# WIFI.net
KiCad netlist of a schematic drawn in Altium Designer
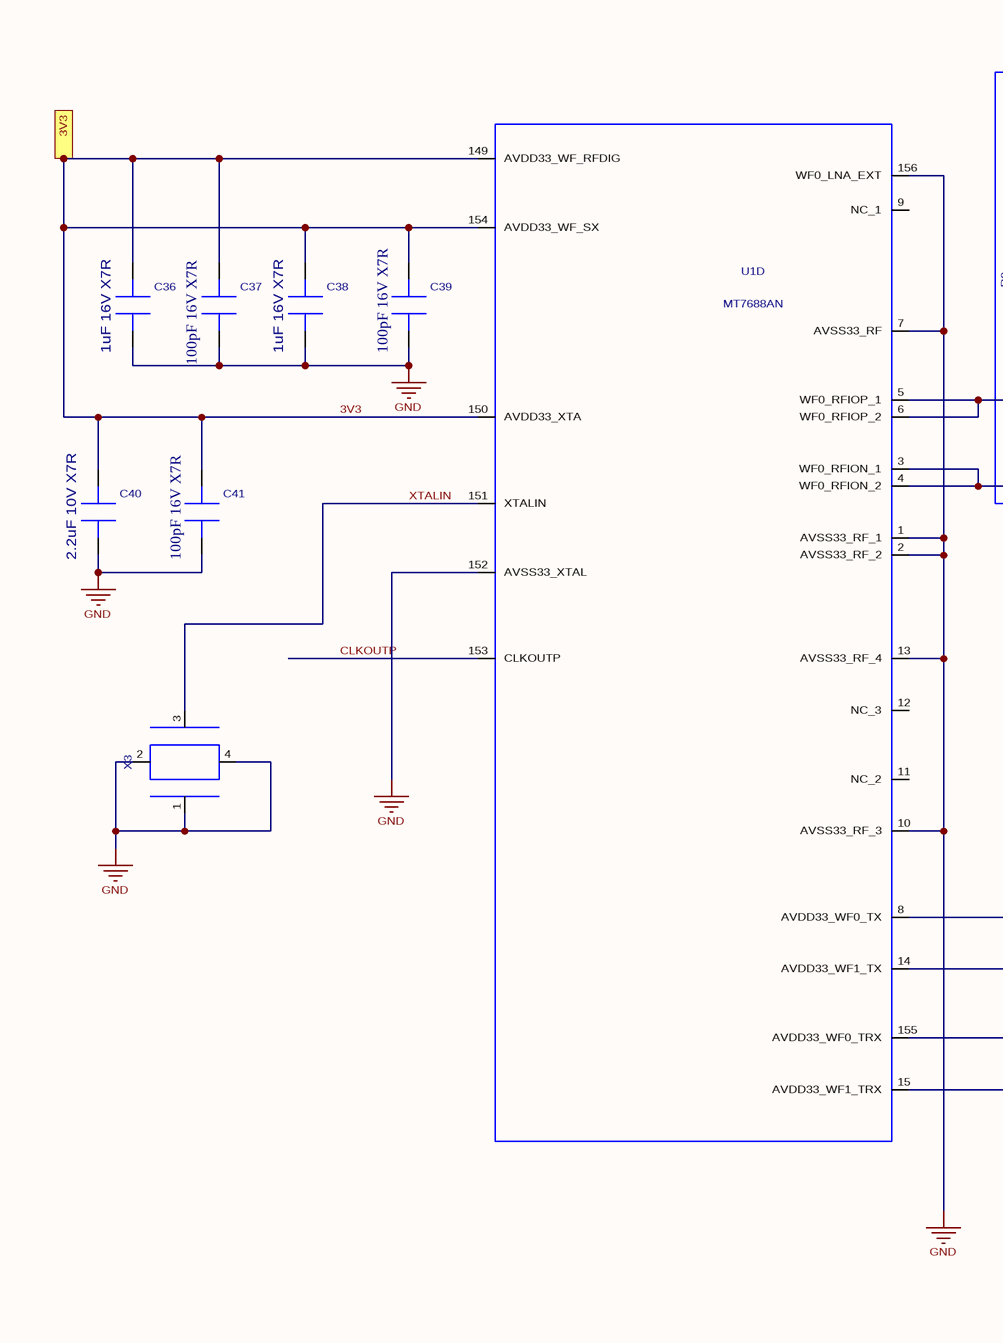
[diagram p0: WIFI.SchDoc, left]
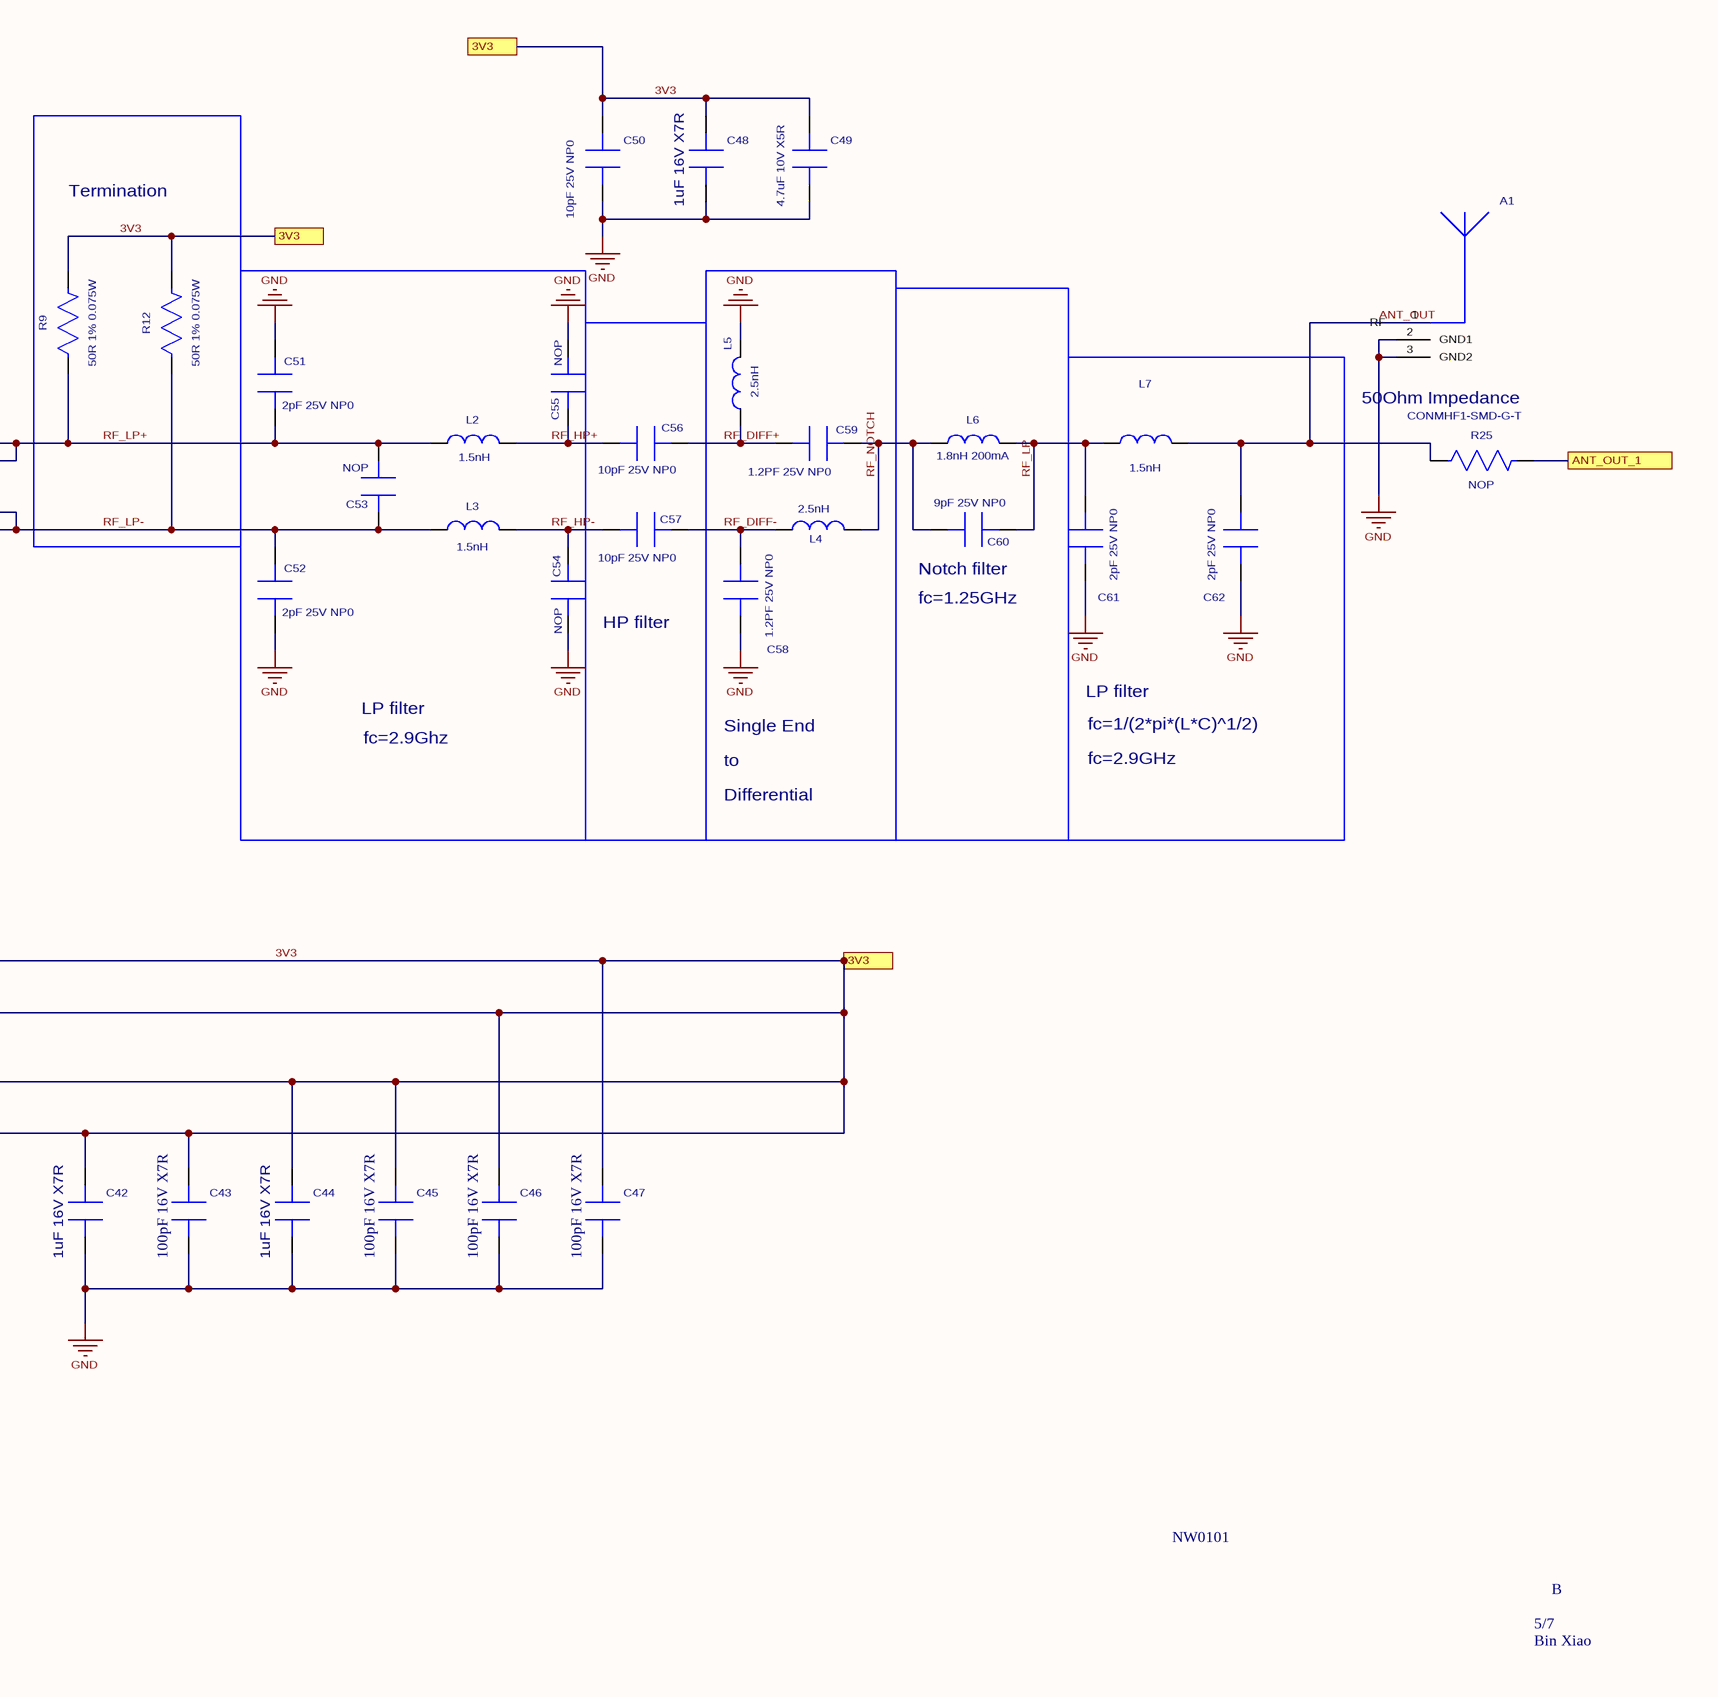
[diagram p1: WIFI.SchDoc, right]

(export (version "E")
  (design (tool "Eeschema 10.0.6"))
  (components
    (comp (ref "A1")
      (value "CONMHF1-SMD-G-T")
      (footprint "CONMHF1-SMD-G-T")
      (description "CONN UMC JACK STR SMD")
      (fields (field (name "MANUFACTURER") "Linx Technologies Inc."))
      (libsource (lib "*") (part "CONMHF1-SMD-G-T"))
    )
    (comp (ref "C36")
      (value "1uF 16V X7R")
      (footprint "C0402")
      (description "CAP CER 1UF 6.3V X7R 0402")
      (fields
        (field (name "PART NUMBER") "GRM155R70J105KA12D")
        (field (name "MANUFACTURER") "Murata Electronics")
      )
      (libsource (lib "NetworkModule") (part "CAP0402-105-6.3V-X7R"))
    )
    (comp (ref "C37")
      (value "100pF 16V X7R")
      (footprint "C0201")
      (description "CAP CER 100PF 16V X7R 0201")
      (fields
        (field (name "PART NUMBER") "0201B101K160CT")
        (field (name "MANUFACTURER") "Walsin Technology Corporation")
      )
      (libsource (lib "NetworkModule") (part "CAP0201-101-16V-X7R"))
    )
    (comp (ref "C38")
      (value "1uF 16V X7R")
      (footprint "C0402")
      (description "CAP CER 1UF 6.3V X7R 0402")
      (fields
        (field (name "PART NUMBER") "GRM155R70J105KA12D")
        (field (name "MANUFACTURER") "Murata Electronics")
      )
      (libsource (lib "NetworkModule") (part "CAP0402-105-6.3V-X7R"))
    )
    (comp (ref "C39")
      (value "100pF 16V X7R")
      (footprint "C0201")
      (description "CAP CER 100PF 16V X7R 0201")
      (fields
        (field (name "PART NUMBER") "0201B101K160CT")
        (field (name "MANUFACTURER") "Walsin Technology Corporation")
      )
      (libsource (lib "NetworkModule") (part "CAP0201-101-16V-X7R"))
    )
    (comp (ref "C40")
      (value "2.2uF 10V X7R")
      (footprint "C0402")
      (description "CAP CER 2.2UF 10V X7R 0402")
      (fields
        (field (name "PART NUMBER") "GRM155Z71A225KE01D")
        (field (name "MANUFACTURER") "Murata Electronics")
      )
      (libsource (lib "NetworkModule") (part "CAP0402-225-6.3V-X7R"))
    )
    (comp (ref "C41")
      (value "100pF 16V X7R")
      (footprint "C0201")
      (description "CAP CER 100PF 16V X7R 0201")
      (fields
        (field (name "PART NUMBER") "0201B101K160CT")
        (field (name "MANUFACTURER") "Walsin Technology Corporation")
      )
      (libsource (lib "NetworkModule") (part "CAP0201-101-16V-X7R"))
    )
    (comp (ref "C42")
      (value "1uF 16V X7R")
      (footprint "C0402")
      (description "CAP CER 1UF 6.3V X7R 0402")
      (fields
        (field (name "PART NUMBER") "GRM155R70J105KA12D")
        (field (name "MANUFACTURER") "Murata Electronics")
      )
      (libsource (lib "NetworkModule") (part "CAP0402-105-6.3V-X7R"))
    )
    (comp (ref "C43")
      (value "100pF 16V X7R")
      (footprint "C0201")
      (description "CAP CER 100PF 16V X7R 0201")
      (fields
        (field (name "PART NUMBER") "0201B101K160CT")
        (field (name "MANUFACTURER") "Walsin Technology Corporation")
      )
      (libsource (lib "NetworkModule") (part "CAP0201-101-16V-X7R"))
    )
    (comp (ref "C44")
      (value "1uF 16V X7R")
      (footprint "C0402")
      (description "CAP CER 1UF 6.3V X7R 0402")
      (fields
        (field (name "PART NUMBER") "GRM155R70J105KA12D")
        (field (name "MANUFACTURER") "Murata Electronics")
      )
      (libsource (lib "NetworkModule") (part "CAP0402-105-6.3V-X7R"))
    )
    (comp (ref "C45")
      (value "100pF 16V X7R")
      (footprint "C0201")
      (description "CAP CER 100PF 16V X7R 0201")
      (fields
        (field (name "PART NUMBER") "0201B101K160CT")
        (field (name "MANUFACTURER") "Walsin Technology Corporation")
      )
      (libsource (lib "NetworkModule") (part "CAP0201-101-16V-X7R"))
    )
    (comp (ref "C46")
      (value "100pF 16V X7R")
      (footprint "C0201")
      (description "CAP CER 100PF 16V X7R 0201")
      (fields
        (field (name "PART NUMBER") "0201B101K160CT")
        (field (name "MANUFACTURER") "Walsin Technology Corporation")
      )
      (libsource (lib "NetworkModule") (part "CAP0201-101-16V-X7R"))
    )
    (comp (ref "C47")
      (value "100pF 16V X7R")
      (footprint "C0201")
      (description "CAP CER 100PF 16V X7R 0201")
      (fields
        (field (name "PART NUMBER") "0201B101K160CT")
        (field (name "MANUFACTURER") "Walsin Technology Corporation")
      )
      (libsource (lib "NetworkModule") (part "CAP0201-101-16V-X7R"))
    )
    (comp (ref "C48")
      (value "1uF 16V X7R")
      (footprint "C0402")
      (description "CAP CER 1UF 6.3V X7R 0402")
      (fields
        (field (name "PART NUMBER") "GRM155R70J105KA12D")
        (field (name "MANUFACTURER") "Murata Electronics")
      )
      (libsource (lib "NetworkModule") (part "CAP0402-105-6.3V-X7R"))
    )
    (comp (ref "C49")
      (value "4.7uF 10V X5R")
      (footprint "C0402")
      (description "CAP CER 4.7UF 10V X5R 0402")
      (fields
        (field (name "PART NUMBER") "CL05A475MP5NRNC")
        (field (name "MANUFACTURER") "Samsung Electro-Mechanics")
      )
      (libsource (lib "NetworkModule") (part "CAP0402-475-10V-X5R"))
    )
    (comp (ref "C50")
      (value "10pF 25V NP0")
      (footprint "C0201")
      (description "CAP CER 10PF 25V C0G/NP0 0201")
      (fields
        (field (name "PART NUMBER") "0201N100J250CT")
        (field (name "MANUFACTURER") "Walsin Technology Corporation")
      )
      (libsource (lib "NetworkModule") (part "CAP0201-100-25V-NP0"))
    )
    (comp (ref "C51")
      (value "2pF 25V NP0")
      (footprint "C0201")
      (description "CAP CER 2PF 25V C0G/NP0 0201")
      (fields
        (field (name "PART NUMBER") "CL03C020BA3GNNC")
        (field (name "MANUFACTURER") "Samsung Electro-Mechanics")
      )
      (libsource (lib "NetworkModule") (part "CAP0201-020-25V-NP0"))
    )
    (comp (ref "C52")
      (value "2pF 25V NP0")
      (footprint "C0201")
      (description "CAP CER 2PF 25V C0G/NP0 0201")
      (fields
        (field (name "PART NUMBER") "CL03C020BA3GNNC")
        (field (name "MANUFACTURER") "Samsung Electro-Mechanics")
      )
      (libsource (lib "NetworkModule") (part "CAP0201-020-25V-NP0"))
    )
    (comp (ref "C53")
      (value "NOP")
      (footprint "C0201_NOP")
      (fields (field (name "Comment") "CAP0201-NOP"))
      (libsource (lib "NetworkModule") (part "CAP0201-NOP"))
    )
    (comp (ref "C54")
      (value "NOP")
      (footprint "C0201_NOP")
      (fields (field (name "Comment") "CAP0201-NOP"))
      (libsource (lib "NetworkModule") (part "CAP0201-NOP"))
    )
    (comp (ref "C55")
      (value "NOP")
      (footprint "C0201_NOP")
      (fields (field (name "Comment") "CAP0201-NOP"))
      (libsource (lib "NetworkModule") (part "CAP0201-NOP"))
    )
    (comp (ref "C56")
      (value "10pF 25V NP0")
      (footprint "C0201")
      (description "CAP CER 10PF 25V C0G/NP0 0201")
      (fields
        (field (name "PART NUMBER") "0201N100J250CT")
        (field (name "MANUFACTURER") "Walsin Technology Corporation")
      )
      (libsource (lib "NetworkModule") (part "CAP0201-100-25V-NP0"))
    )
    (comp (ref "C57")
      (value "10pF 25V NP0")
      (footprint "C0201")
      (description "CAP CER 10PF 25V C0G/NP0 0201")
      (fields
        (field (name "PART NUMBER") "0201N100J250CT")
        (field (name "MANUFACTURER") "Walsin Technology Corporation")
      )
      (libsource (lib "NetworkModule") (part "CAP0201-100-25V-NP0"))
    )
    (comp (ref "C58")
      (value "1.2PF 25V NP0")
      (footprint "C0201")
      (description "CAP CER 1.2PF 25V C0G/NP0 0201")
      (fields
        (field (name "PART NUMBER") "GRM0335C1E1R2WA01D")
        (field (name "MANUFACTURER") "Murata Electronics")
      )
      (libsource (lib "NetworkModule") (part "CAP0201-1R2-25V-NP0"))
    )
    (comp (ref "C59")
      (value "1.2PF 25V NP0")
      (footprint "C0201")
      (description "CAP CER 1.2PF 25V C0G/NP0 0201")
      (fields
        (field (name "PART NUMBER") "GRM0335C1E1R2WA01D")
        (field (name "MANUFACTURER") "Murata Electronics")
      )
      (libsource (lib "NetworkModule") (part "CAP0201-1R2-25V-NP0"))
    )
    (comp (ref "C60")
      (value "9pF 25V NP0")
      (footprint "C0201")
      (description "CAP CER 9PF 25V C0G 0201")
      (fields
        (field (name "PART NUMBER") "CGA1A2C0G1E090D030BA")
        (field (name "MANUFACTURER") "TDK Corporation")
      )
      (libsource (lib "NetworkModule") (part "CAP0201-090-100V-NP0"))
    )
    (comp (ref "C61")
      (value "2pF 25V NP0")
      (footprint "C0201")
      (description "CAP CER 2PF 25V C0G/NP0 0201")
      (fields
        (field (name "PART NUMBER") "CL03C020BA3GNNC")
        (field (name "MANUFACTURER") "Samsung Electro-Mechanics")
      )
      (libsource (lib "NetworkModule") (part "CAP0201-020-25V-NP0"))
    )
    (comp (ref "C62")
      (value "2pF 25V NP0")
      (footprint "C0201")
      (description "CAP CER 2PF 25V C0G/NP0 0201")
      (fields
        (field (name "PART NUMBER") "CL03C020BA3GNNC")
        (field (name "MANUFACTURER") "Samsung Electro-Mechanics")
      )
      (libsource (lib "NetworkModule") (part "CAP0201-020-25V-NP0"))
    )
    (comp (ref "L2")
      (value "1.5nH")
      (footprint "L0201")
      (description "INDUCTOR FIXED 1.5NH 0201")
      (fields
        (field (name "PART NUMBER") "WLCM0603TGB1N5TB")
        (field (name "MANUFACTURER") "Walsin Technology Corporation")
      )
      (libsource (lib "NetworkModule") (part "IND0201_1.5N_600MA"))
    )
    (comp (ref "L3")
      (value "1.5nH")
      (footprint "L0201")
      (description "INDUCTOR FIXED 1.5NH 0201")
      (fields
        (field (name "PART NUMBER") "WLCM0603TGB1N5TB")
        (field (name "MANUFACTURER") "Walsin Technology Corporation")
      )
      (libsource (lib "NetworkModule") (part "IND0201_1.5N_600MA"))
    )
    (comp (ref "L4")
      (value "2.5nH")
      (footprint "L0201")
      (description "FIXED IND 2.5NH 500MA 200MOHM SM")
      (fields
        (field (name "PART NUMBER") "LQP03TN2N5B02D")
        (field (name "MANUFACTURER") "Murata Electronics")
      )
      (libsource (lib "NetworkModule") (part "IND0201_2.5N_500MA"))
    )
    (comp (ref "L5")
      (value "2.5nH")
      (footprint "L0201")
      (description "FIXED IND 2.5NH 500MA 200MOHM SM")
      (fields
        (field (name "PART NUMBER") "LQP03TN2N5B02D")
        (field (name "MANUFACTURER") "Murata Electronics")
      )
      (libsource (lib "NetworkModule") (part "IND0201_2.5N_500MA"))
    )
    (comp (ref "L6")
      (value "1.8nH 200mA")
      (footprint "L0201")
      (description "FIXED IND 1.8NH 200MA 550MOHM SM")
      (fields
        (field (name "PART NUMBER") "1-2176075-8")
        (field (name "MANUFACTURER") "TE Connectivity Passive Product")
      )
      (libsource (lib "NetworkModule") (part "IND0201_1.8N_200MA"))
    )
    (comp (ref "L7")
      (value "1.5nH")
      (footprint "L0201")
      (description "INDUCTOR FIXED 1.5NH 0201")
      (fields
        (field (name "PART NUMBER") "WLCM0603TGB1N5TB")
        (field (name "MANUFACTURER") "Walsin Technology Corporation")
      )
      (libsource (lib "NetworkModule") (part "IND0201_1.5N_600MA"))
    )
    (comp (ref "R9")
      (value "50R 1% 0.075W")
      (footprint "R0201")
      (description "RES 50 OHM 0.1% 0.075W 0201")
      (fields (field (name "MANUFACTURER") "Vishay Dale") (field (name "PART NUMBER") "TNPW020150R0BEED"))
      (libsource (lib "NetworkModule") (part "RES0201-50R0"))
    )
    (comp (ref "R12")
      (value "50R 1% 0.075W")
      (footprint "R0201")
      (description "RES 50 OHM 0.1% 0.075W 0201")
      (fields (field (name "MANUFACTURER") "Vishay Dale") (field (name "PART NUMBER") "TNPW020150R0BEED"))
      (libsource (lib "NetworkModule") (part "RES0201-50R0"))
    )
    (comp (ref "R25")
      (value "NOP")
      (footprint "R0201_NOP")
      (fields (field (name "Comment") "RES0201-NOP"))
      (libsource (lib "NetworkModule") (part "RES0201-NOP"))
    )
    (comp (ref "U1")
      (value "MT7688AN")
      (footprint "DR-QFN-128")
      (description "580Mhz 32bits Networking Processor")
      (fields (field (name "MANUFACTURER") "MediaTek Inc"))
      (libsource (lib "*") (part "MT7688AN"))
    )
    (comp (ref "X3")
      (value "R2520-40.000-12-F-1010-TR-NS1")
      (footprint "R2520-40.000-12-F-1010-TR-NS1")
      (description "CRYSTAL 40.0000MHZ 12PF SMD")
      (fields (field (name "MANUFACTURER") "Raltron Electronics"))
      (libsource (lib "*") (part "R2520-40.000-12-F-1010-TR-NS1"))
    )
  )
  (nets
    (net (code "1") (name "/3V3") (class "Default")
      (node (ref "C36") (pin "1") (pinfunction "1_1") (pintype "passive"))
      (node (ref "C37") (pin "1") (pinfunction "1_1") (pintype "passive"))
      (node (ref "C38") (pin "1") (pinfunction "1_1") (pintype "passive"))
      (node (ref "C39") (pin "1") (pinfunction "1_1") (pintype "passive"))
      (node (ref "C40") (pin "1") (pinfunction "1_1") (pintype "passive"))
      (node (ref "C41") (pin "1") (pinfunction "1_1") (pintype "passive"))
      (node (ref "C42") (pin "1") (pinfunction "1_1") (pintype "passive"))
      (node (ref "C43") (pin "1") (pinfunction "1_1") (pintype "passive"))
      (node (ref "C44") (pin "1") (pinfunction "1_1") (pintype "passive"))
      (node (ref "C45") (pin "1") (pinfunction "1_1") (pintype "passive"))
      (node (ref "C46") (pin "1") (pinfunction "1_1") (pintype "passive"))
      (node (ref "C47") (pin "1") (pinfunction "1_1") (pintype "passive"))
      (node (ref "C48") (pin "1") (pinfunction "1_1") (pintype "passive"))
      (node (ref "C49") (pin "1") (pinfunction "1_1") (pintype "passive"))
      (node (ref "C50") (pin "1") (pinfunction "1_1") (pintype "passive"))
      (node (ref "R12") (pin "2") (pinfunction "2_2") (pintype "passive"))
      (node (ref "R9") (pin "2") (pinfunction "2_2") (pintype "passive"))
      (node (ref "U1") (pin "14") (pinfunction "AVDD33_WF1_TX_14") (pintype "passive"))
      (node (ref "U1") (pin "149") (pinfunction "AVDD33_WF_RFDIG_149") (pintype "passive"))
      (node (ref "U1") (pin "15") (pinfunction "AVDD33_WF1_TRX_15") (pintype "passive"))
      (node (ref "U1") (pin "150") (pinfunction "AVDD33_XTA_150") (pintype "passive"))
      (node (ref "U1") (pin "154") (pinfunction "AVDD33_WF_SX_154") (pintype "passive"))
      (node (ref "U1") (pin "155") (pinfunction "AVDD33_WF0_TRX_155") (pintype "passive"))
      (node (ref "U1") (pin "8") (pinfunction "AVDD33_WF0_TX_8") (pintype "passive"))
    )
    (net (code "2") (name "/ANT_OUT") (class "Default")
      (node (ref "A1") (pin "1") (pinfunction "RF_1") (pintype "passive"))
      (node (ref "C62") (pin "1") (pinfunction "1_1") (pintype "passive"))
      (node (ref "L7") (pin "2") (pinfunction "2_2") (pintype "passive"))
      (node (ref "R25") (pin "1") (pinfunction "1_1") (pintype "passive"))
    )
    (net (code "3") (name "/ANT_OUT_1") (class "Default")
      (node (ref "R25") (pin "2") (pinfunction "2_2") (pintype "passive"))
    )
    (net (code "4") (name "/CLKOUTP") (class "Default")
      (node (ref "U1") (pin "153") (pinfunction "CLKOUTP_153") (pintype "passive"))
    )
    (net (code "5") (name "/RF_DIFF+") (class "Default")
      (node (ref "C56") (pin "1") (pinfunction "1_1") (pintype "passive"))
      (node (ref "C59") (pin "2") (pinfunction "2_2") (pintype "passive"))
      (node (ref "L5") (pin "1") (pinfunction "1_1") (pintype "passive"))
    )
    (net (code "6") (name "/RF_DIFF-") (class "Default")
      (node (ref "C57") (pin "1") (pinfunction "1_1") (pintype "passive"))
      (node (ref "C58") (pin "1") (pinfunction "1_1") (pintype "passive"))
      (node (ref "L4") (pin "1") (pinfunction "1_1") (pintype "passive"))
    )
    (net (code "7") (name "/RF_HP+") (class "Default")
      (node (ref "C55") (pin "1") (pinfunction "1_1") (pintype "passive"))
      (node (ref "C56") (pin "2") (pinfunction "2_2") (pintype "passive"))
      (node (ref "L2") (pin "2") (pinfunction "2_2") (pintype "passive"))
    )
    (net (code "8") (name "/RF_HP-") (class "Default")
      (node (ref "C54") (pin "1") (pinfunction "1_1") (pintype "passive"))
      (node (ref "C57") (pin "2") (pinfunction "2_2") (pintype "passive"))
      (node (ref "L3") (pin "2") (pinfunction "2_2") (pintype "passive"))
    )
    (net (code "9") (name "/RF_LP") (class "Default")
      (node (ref "C60") (pin "1") (pinfunction "1_1") (pintype "passive"))
      (node (ref "C61") (pin "1") (pinfunction "1_1") (pintype "passive"))
      (node (ref "L6") (pin "2") (pinfunction "2_2") (pintype "passive"))
      (node (ref "L7") (pin "1") (pinfunction "1_1") (pintype "passive"))
    )
    (net (code "10") (name "/RF_LP+") (class "Default")
      (node (ref "C51") (pin "2") (pinfunction "2_2") (pintype "passive"))
      (node (ref "C53") (pin "1") (pinfunction "1_1") (pintype "passive"))
      (node (ref "L2") (pin "1") (pinfunction "1_1") (pintype "passive"))
      (node (ref "R9") (pin "1") (pinfunction "1_1") (pintype "passive"))
      (node (ref "U1") (pin "5") (pinfunction "WF0_RFIOP_1_5") (pintype "passive"))
      (node (ref "U1") (pin "6") (pinfunction "WF0_RFIOP_2_6") (pintype "passive"))
    )
    (net (code "11") (name "/RF_LP-") (class "Default")
      (node (ref "C52") (pin "1") (pinfunction "1_1") (pintype "passive"))
      (node (ref "C53") (pin "2") (pinfunction "2_2") (pintype "passive"))
      (node (ref "L3") (pin "1") (pinfunction "1_1") (pintype "passive"))
      (node (ref "R12") (pin "1") (pinfunction "1_1") (pintype "passive"))
      (node (ref "U1") (pin "3") (pinfunction "WF0_RFION_1_3") (pintype "passive"))
      (node (ref "U1") (pin "4") (pinfunction "WF0_RFION_2_4") (pintype "passive"))
    )
    (net (code "12") (name "/RF_NOTCH") (class "Default")
      (node (ref "C59") (pin "1") (pinfunction "1_1") (pintype "passive"))
      (node (ref "C60") (pin "2") (pinfunction "2_2") (pintype "passive"))
      (node (ref "L4") (pin "2") (pinfunction "2_2") (pintype "passive"))
      (node (ref "L6") (pin "1") (pinfunction "1_1") (pintype "passive"))
    )
    (net (code "13") (name "/XTALIN") (class "Default")
      (node (ref "U1") (pin "151") (pinfunction "XTALIN_151") (pintype "passive"))
      (node (ref "X3") (pin "3") (pinfunction "3_3") (pintype "passive"))
    )
    (net (code "14") (name "GND") (class "Default")
      (node (ref "A1") (pin "2") (pinfunction "GND1_2") (pintype "passive"))
      (node (ref "A1") (pin "3") (pinfunction "GND2_3") (pintype "passive"))
      (node (ref "C36") (pin "2") (pinfunction "2_2") (pintype "passive"))
      (node (ref "C37") (pin "2") (pinfunction "2_2") (pintype "passive"))
      (node (ref "C38") (pin "2") (pinfunction "2_2") (pintype "passive"))
      (node (ref "C39") (pin "2") (pinfunction "2_2") (pintype "passive"))
      (node (ref "C40") (pin "2") (pinfunction "2_2") (pintype "passive"))
      (node (ref "C41") (pin "2") (pinfunction "2_2") (pintype "passive"))
      (node (ref "C42") (pin "2") (pinfunction "2_2") (pintype "passive"))
      (node (ref "C43") (pin "2") (pinfunction "2_2") (pintype "passive"))
      (node (ref "C44") (pin "2") (pinfunction "2_2") (pintype "passive"))
      (node (ref "C45") (pin "2") (pinfunction "2_2") (pintype "passive"))
      (node (ref "C46") (pin "2") (pinfunction "2_2") (pintype "passive"))
      (node (ref "C47") (pin "2") (pinfunction "2_2") (pintype "passive"))
      (node (ref "C48") (pin "2") (pinfunction "2_2") (pintype "passive"))
      (node (ref "C49") (pin "2") (pinfunction "2_2") (pintype "passive"))
      (node (ref "C50") (pin "2") (pinfunction "2_2") (pintype "passive"))
      (node (ref "C51") (pin "1") (pinfunction "1_1") (pintype "passive"))
      (node (ref "C52") (pin "2") (pinfunction "2_2") (pintype "passive"))
      (node (ref "C54") (pin "2") (pinfunction "2_2") (pintype "passive"))
      (node (ref "C55") (pin "2") (pinfunction "2_2") (pintype "passive"))
      (node (ref "C58") (pin "2") (pinfunction "2_2") (pintype "passive"))
      (node (ref "C61") (pin "2") (pinfunction "2_2") (pintype "passive"))
      (node (ref "C62") (pin "2") (pinfunction "2_2") (pintype "passive"))
      (node (ref "L5") (pin "2") (pinfunction "2_2") (pintype "passive"))
      (node (ref "U1") (pin "1") (pinfunction "AVSS33_RF_1_1") (pintype "passive"))
      (node (ref "U1") (pin "10") (pinfunction "AVSS33_RF_3_10") (pintype "passive"))
      (node (ref "U1") (pin "13") (pinfunction "AVSS33_RF_4_13") (pintype "passive"))
      (node (ref "U1") (pin "152") (pinfunction "AVSS33_XTAL_152") (pintype "passive"))
      (node (ref "U1") (pin "156") (pinfunction "WF0_LNA_EXT_156") (pintype "passive"))
      (node (ref "U1") (pin "2") (pinfunction "AVSS33_RF_2_2") (pintype "passive"))
      (node (ref "U1") (pin "7") (pinfunction "AVSS33_RF_7") (pintype "passive"))
      (node (ref "X3") (pin "1") (pinfunction "1_1") (pintype "passive"))
      (node (ref "X3") (pin "2") (pinfunction "GND1_2") (pintype "passive"))
      (node (ref "X3") (pin "4") (pinfunction "GND2_4") (pintype "passive"))
    )
    (net (code "15") (name "unconnected-(U1D-NC_1-Pad9)") (class "Default")
      (node (ref "U1") (pin "9") (pinfunction "NC_1_9") (pintype "passive"))
    )
    (net (code "16") (name "unconnected-(U1D-NC_2-Pad11)") (class "Default")
      (node (ref "U1") (pin "11") (pinfunction "NC_2_11") (pintype "passive"))
    )
    (net (code "17") (name "unconnected-(U1D-NC_3-Pad12)") (class "Default")
      (node (ref "U1") (pin "12") (pinfunction "NC_3_12") (pintype "passive"))
    )
  )
)
